# EFD01_-_C_Feeder.net
KiCad netlist of a schematic drawn in EAGLE
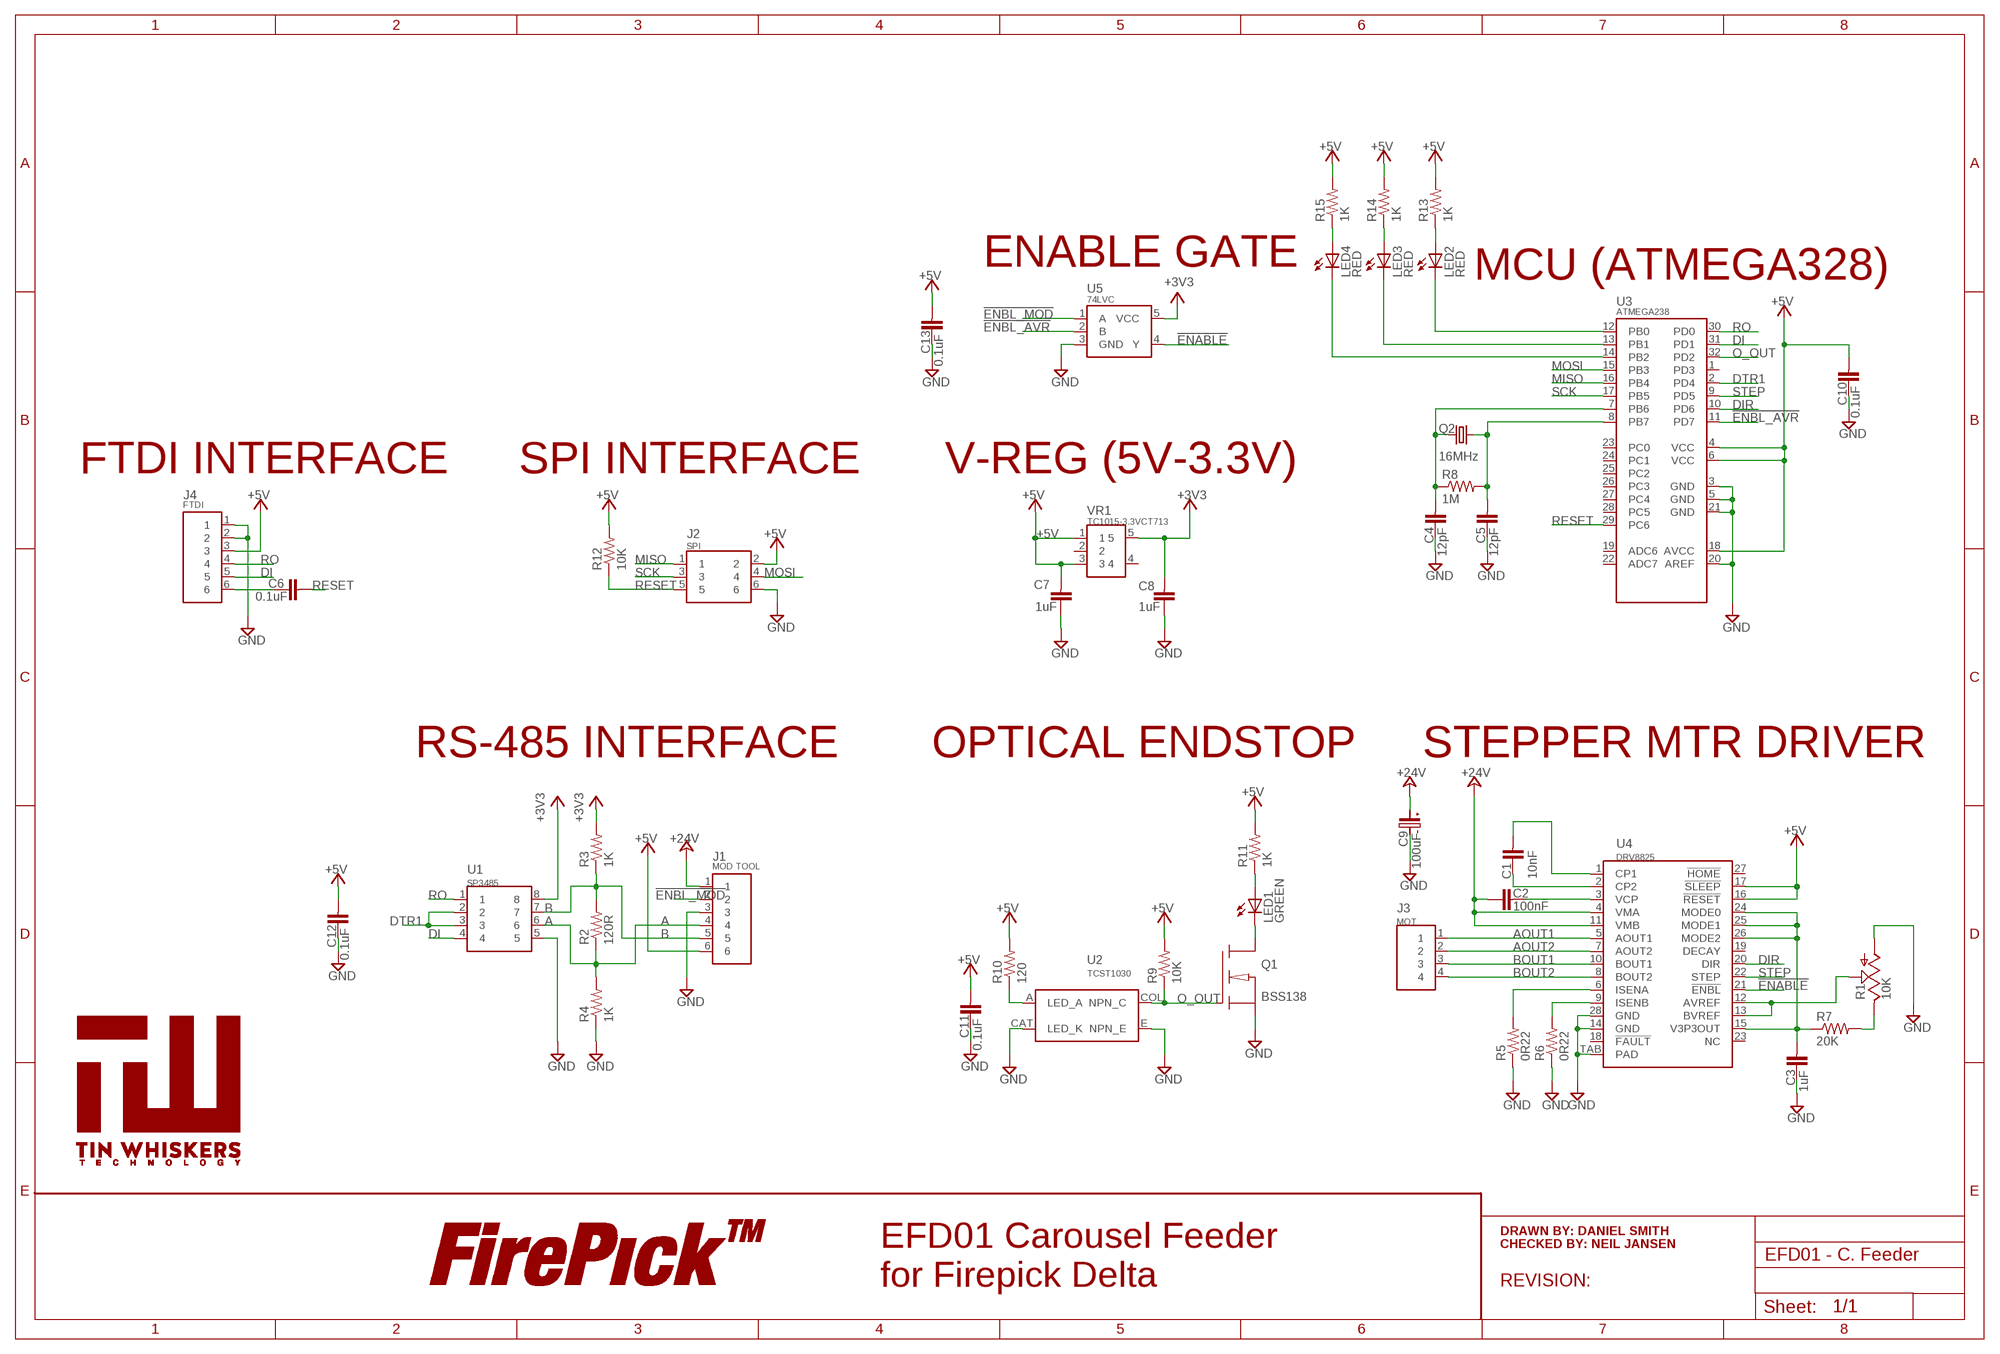
[diagram p0: schematic, sheet 1]

(export (version "E")
  (design (tool "Eeschema 10.0.6"))
  (components
    (comp (ref "C1")
      (value "10nF")
      (footprint "eagle-import:C0603")
      (fields (field (name "PARTNO") "GRM188R71H103KA01D"))
      (libsource (lib "eagle-import") (part "CPL-CAP-X7R-0603-10NF-50V"))
    )
    (comp (ref "C2")
      (value "100nF")
      (footprint "eagle-import:C0603")
      (fields (field (name "PARTNO") "UMK107B7104KA-T"))
      (libsource (lib "eagle-import") (part "CPL-CAP-X7R-0603-100NF-50V"))
    )
    (comp (ref "C3")
      (value "1uF")
      (footprint "eagle-import:C0603")
      (fields (field (name "PARTNO") "UMK107AB7105KA-T"))
      (libsource (lib "eagle-import") (part "CPL-CAP-X5R-0603-1UF-50V"))
    )
    (comp (ref "C4")
      (value "12pF")
      (footprint "eagle-import:C0603")
      (fields (field (name "PARTNO") "GRM1885C1H120FA01J"))
      (libsource (lib "eagle-import") (part "CPL-CAP-C0G-0603-12PF-50V"))
    )
    (comp (ref "C5")
      (value "12pF")
      (footprint "eagle-import:C0603")
      (fields (field (name "PARTNO") "GRM1885C1H120FA01J"))
      (libsource (lib "eagle-import") (part "CPL-CAP-C0G-0603-12PF-50V"))
    )
    (comp (ref "C6")
      (value "0.1uF")
      (footprint "eagle-import:C0603")
      (fields (field (name "PARTNO") "UMK107B7104KA-T"))
      (libsource (lib "eagle-import") (part "CPL-CAP-X7R-0603-100NF-50V"))
    )
    (comp (ref "C7")
      (value "1uF")
      (footprint "eagle-import:C0603")
      (fields (field (name "PARTNO") "UMK107AB7105KA-T"))
      (libsource (lib "eagle-import") (part "CPL-CAP-X5R-0603-1UF-50V"))
    )
    (comp (ref "C8")
      (value "1uF")
      (footprint "eagle-import:C0603")
      (fields (field (name "PARTNO") "UMK107AB7105KA-T"))
      (libsource (lib "eagle-import") (part "CPL-CAP-X5R-0603-1UF-50V"))
    )
    (comp (ref "C9")
      (value "100uF")
      (footprint "eagle-import:C-SMD-6.3MM")
      (fields (field (name "PARTNO") "EMVA500ADA101MHA0G"))
      (libsource (lib "eagle-import") (part "CPL-CAP-ALU-SMD-100UF-50V"))
    )
    (comp (ref "C10")
      (value "0.1uF")
      (footprint "eagle-import:C0603")
      (fields (field (name "PARTNO") "UMK107B7104KA-T"))
      (libsource (lib "eagle-import") (part "CPL-CAP-X7R-0603-0.1UF-35V"))
    )
    (comp (ref "C11")
      (value "0.1uF")
      (footprint "eagle-import:C0603")
      (fields (field (name "PARTNO") "UMK107B7104KA-T"))
      (libsource (lib "eagle-import") (part "CPL-CAP-X7R-0603-0.1UF-35V"))
    )
    (comp (ref "C12")
      (value "0.1uF")
      (footprint "eagle-import:C0603")
      (fields (field (name "PARTNO") "UMK107B7104KA-T"))
      (libsource (lib "eagle-import") (part "CPL-CAP-X7R-0603-0.1UF-35V"))
    )
    (comp (ref "C13")
      (value "0.1uF")
      (footprint "eagle-import:C0603")
      (fields (field (name "PARTNO") "UMK107B7104KA-T"))
      (libsource (lib "eagle-import") (part "CPL-CAP-X7R-0603-0.1UF-35V"))
    )
    (comp (ref "J1")
      (value "MOD TOOL")
      (footprint "eagle-import:CONN-JST-PH-2.0MM-6P-SMT-RA")
      (fields (field (name "PARTNO") "S6B-PH-SM4-TB(LF)(SN)"))
      (libsource (lib "eagle-import") (part "CPL-CON-JST-2.0MM-6P-M-RA"))
    )
    (comp (ref "J2")
      (value "SPI")
      (footprint "eagle-import:CON-HDR-2X3P")
      (fields (field (name "PARTNO") "67996-206HLF"))
      (libsource (lib "eagle-import") (part "CPL-CON-HEADER-0.1IN-2X3P-M"))
    )
    (comp (ref "J3")
      (value "MOT")
      (footprint "eagle-import:CONN-JST-PH-2.0MM-4P-SMT-RA")
      (fields (field (name "PARTNO") "S4B-PH-SM4-TB(LF)(SN)"))
      (libsource (lib "eagle-import") (part "CPL-CON-JST-2.0MM-4P-M-RA"))
    )
    (comp (ref "J4")
      (value "FTDI")
      (footprint "eagle-import:CON-HDR-6POS-MALE")
      (fields (field (name "PARTNO") "S6B-PH-SM4-TB(LF)(SN)"))
      (libsource (lib "eagle-import") (part "CPL-CON-HEADER-0.1IN-6P-M"))
    )
    (comp (ref "LED1")
      (value "GREEN")
      (footprint "eagle-import:LED0603")
      (fields (field (name "PARTNO") "SML-D12M8WT86"))
      (libsource (lib "eagle-import") (part "CPL-LED-0603-GREEN"))
    )
    (comp (ref "LED2")
      (value "RED")
      (footprint "eagle-import:LED0603")
      (fields (field (name "PARTNO") "SML-D12M8WT86"))
      (libsource (lib "eagle-import") (part "CPL-LED-0603-RED"))
    )
    (comp (ref "LED3")
      (value "RED")
      (footprint "eagle-import:LED0603")
      (fields (field (name "PARTNO") "SML-D12M8WT86"))
      (libsource (lib "eagle-import") (part "CPL-LED-0603-RED"))
    )
    (comp (ref "LED4")
      (value "RED")
      (footprint "eagle-import:LED0603")
      (fields (field (name "PARTNO") "SML-D12M8WT86"))
      (libsource (lib "eagle-import") (part "CPL-LED-0603-RED"))
    )
    (comp (ref "LOGO2")
      (value "LOGO-FIREPICKLARGE")
      (footprint "eagle-import:LOGO-FIREPICK")
      (libsource (lib "eagle-import") (part "LOGO-FIREPICKLARGE"))
    )
    (comp (ref "Q1")
      (value "BSS138")
      (footprint "eagle-import:SOT-23-3")
      (libsource (lib "eagle-import") (part "CPL-TRN-NFET-SOT23"))
    )
    (comp (ref "Q2")
      (value "16MHz")
      (footprint "eagle-import:HC-49_U-S")
      (fields (field (name "PARTNO") "HCM4916000000ABJT"))
      (libsource (lib "eagle-import") (part "CPL-OSC-CRY-16MHZ-18PF"))
    )
    (comp (ref "R1")
      (value "10K")
      (footprint "eagle-import:TC33X-2")
      (fields (field (name "PARTNO") "TC33X-2-103E"))
      (libsource (lib "eagle-import") (part "TC33X-2"))
    )
    (comp (ref "R2")
      (value "120R")
      (footprint "eagle-import:R0603")
      (fields (field (name "PARTNO") "RC0603FR-07120RL"))
      (libsource (lib "eagle-import") (part "CPL-RES-0603-120-0.1W"))
    )
    (comp (ref "R3")
      (value "1K")
      (footprint "eagle-import:R0603")
      (fields (field (name "PARTNO") "RC0603FR-071KL"))
      (libsource (lib "eagle-import") (part "CPL-RES-0603-1K-0.1W"))
    )
    (comp (ref "R4")
      (value "1K")
      (footprint "eagle-import:R0603")
      (fields (field (name "PARTNO") "RC0603FR-071KL"))
      (libsource (lib "eagle-import") (part "CPL-RES-0603-1K-0.1W"))
    )
    (comp (ref "R5")
      (value "0R22")
      (footprint "eagle-import:R1206")
      (fields (field (name "PARTNO") "RL1206FR-7W0R22L"))
      (libsource (lib "eagle-import") (part "CPL-RES-1206-0.22-0.5W"))
    )
    (comp (ref "R6")
      (value "0R22")
      (footprint "eagle-import:R1206")
      (fields (field (name "PARTNO") "RL1206FR-7W0R22L"))
      (libsource (lib "eagle-import") (part "CPL-RES-1206-0.22-0.5W"))
    )
    (comp (ref "R7")
      (value "20K")
      (footprint "eagle-import:R0603")
      (fields (field (name "PARTNO") "RC0603FR-0722KL"))
      (libsource (lib "eagle-import") (part "CPL-RES-0603-20K-0.1W"))
    )
    (comp (ref "R8")
      (value "1M")
      (footprint "eagle-import:R0603")
      (fields (field (name "PARTNO") "RC0603FR-071ML"))
      (libsource (lib "eagle-import") (part "CPL-RES-0603-1M-0.1W"))
    )
    (comp (ref "R9")
      (value "10K")
      (footprint "eagle-import:R0603")
      (fields (field (name "PARTNO") "RC0603FR-0710KL"))
      (libsource (lib "eagle-import") (part "CPL-RES-0603-10K-0.1W"))
    )
    (comp (ref "R10")
      (value "120")
      (footprint "eagle-import:R0603")
      (fields (field (name "PARTNO") "RC0603FR-07120RL"))
      (libsource (lib "eagle-import") (part "CPL-RES-0603-120-0.1W"))
    )
    (comp (ref "R11")
      (value "1K")
      (footprint "eagle-import:R0603")
      (fields (field (name "PARTNO") "RC0603FR-071KL"))
      (libsource (lib "eagle-import") (part "CPL-RES-0603-1K-0.1W"))
    )
    (comp (ref "R12")
      (value "10K")
      (footprint "eagle-import:R0603")
      (fields (field (name "PARTNO") "RC0603FR-0710KL"))
      (libsource (lib "eagle-import") (part "CPL-RES-0603-10K-0.1W"))
    )
    (comp (ref "R13")
      (value "1K")
      (footprint "eagle-import:R0603")
      (fields (field (name "PARTNO") "RC0603FR-071KL"))
      (libsource (lib "eagle-import") (part "CPL-RES-0603-1K-0.1W"))
    )
    (comp (ref "R14")
      (value "1K")
      (footprint "eagle-import:R0603")
      (fields (field (name "PARTNO") "RC0603FR-071KL"))
      (libsource (lib "eagle-import") (part "CPL-RES-0603-1K-0.1W"))
    )
    (comp (ref "R15")
      (value "1K")
      (footprint "eagle-import:R0603")
      (fields (field (name "PARTNO") "RC0603FR-071KL"))
      (libsource (lib "eagle-import") (part "CPL-RES-0603-1K-0.1W"))
    )
    (comp (ref "U$1")
      (value "TIN-WHISKERSSMALL")
      (footprint "eagle-import:TIN-WHISKERS-SMALL")
      (libsource (lib "eagle-import") (part "TIN-WHISKERSSMALL"))
    )
    (comp (ref "U1")
      (value "SP3485")
      (footprint "eagle-import:SOICN-8")
      (libsource (lib "eagle-import") (part "SP3485"))
    )
    (comp (ref "U2")
      (value "TCST1030")
      (footprint "eagle-import:TCST1030")
      (libsource (lib "eagle-import") (part "TCSTXX30"))
    )
    (comp (ref "U3")
      (value "ATMEGA238")
      (footprint "eagle-import:32-TQF(ATMEGA)")
      (fields (field (name "PARTNO") "ATMEGA328-AUR"))
      (libsource (lib "eagle-import") (part "CPL-MCU-ATMEL-AT328-32TQFP"))
    )
    (comp (ref "U4")
      (value "DRV8825")
      (footprint "eagle-import:28-HSSOP")
      (fields (field (name "PARTNO") "DRV8825PWPR"))
      (libsource (lib "eagle-import") (part "CPL-MDR-DRV8825"))
    )
    (comp (ref "U5")
      (value "74LVC")
      (footprint "eagle-import:SOT-23-5")
      (fields (field (name "PARTNO") "SN74LVC1G32DBVR"))
      (libsource (lib "eagle-import") (part "CPL-IC-LOGIC-OR-1CH-74LVC"))
    )
    (comp (ref "VR1")
      (value "TC1015-3.3VCT713")
      (footprint "eagle-import:SOT-23-5")
      (libsource (lib "eagle-import") (part "CPL-REG-LIN-3.3V-0.1A"))
    )
  )
  (nets
    (net (code "1") (name "+3V3") (class "Default")
      (node (ref "C8") (pin "2") (pinfunction "2_2") (pintype "passive"))
      (node (ref "R3") (pin "2") (pinfunction "2_2") (pintype "passive"))
      (node (ref "U1") (pin "8") (pinfunction "8_8") (pintype "bidirectional"))
      (node (ref "U5") (pin "5") (pinfunction "VCC_5") (pintype "bidirectional"))
      (node (ref "VR1") (pin "5") (pinfunction "5_5") (pintype "passive"))
    )
    (net (code "2") (name "+5V") (class "Default")
      (node (ref "C10") (pin "2") (pinfunction "2_2") (pintype "passive"))
      (node (ref "C11") (pin "2") (pinfunction "2_2") (pintype "passive"))
      (node (ref "C12") (pin "2") (pinfunction "2_2") (pintype "passive"))
      (node (ref "C13") (pin "2") (pinfunction "2_2") (pintype "passive"))
      (node (ref "C7") (pin "2") (pinfunction "2_2") (pintype "passive"))
      (node (ref "J1") (pin "6") (pinfunction "6_6") (pintype "bidirectional"))
      (node (ref "J2") (pin "2") (pinfunction "2_2") (pintype "passive"))
      (node (ref "J4") (pin "3") (pinfunction "3_3") (pintype "bidirectional"))
      (node (ref "R10") (pin "2") (pinfunction "2_2") (pintype "passive"))
      (node (ref "R11") (pin "2") (pinfunction "2_2") (pintype "passive"))
      (node (ref "R12") (pin "2") (pinfunction "2_2") (pintype "passive"))
      (node (ref "R13") (pin "2") (pinfunction "2_2") (pintype "passive"))
      (node (ref "R14") (pin "2") (pinfunction "2_2") (pintype "passive"))
      (node (ref "R15") (pin "2") (pinfunction "2_2") (pintype "passive"))
      (node (ref "R9") (pin "2") (pinfunction "2_2") (pintype "passive"))
      (node (ref "U3") (pin "18") (pinfunction "AVCC_18") (pintype "bidirectional"))
      (node (ref "U3") (pin "4") (pinfunction "VCC_4") (pintype "bidirectional"))
      (node (ref "U3") (pin "6") (pinfunction "VCC_6") (pintype "bidirectional"))
      (node (ref "U4") (pin "16") (pinfunction "~{RESET}_16") (pintype "bidirectional"))
      (node (ref "U4") (pin "17") (pinfunction "~{SLEEP}_17") (pintype "bidirectional"))
      (node (ref "VR1") (pin "1") (pinfunction "1_1") (pintype "passive"))
      (node (ref "VR1") (pin "3") (pinfunction "3_3") (pintype "passive"))
    )
    (net (code "3") (name "+24V") (class "Default")
      (node (ref "C2") (pin "1") (pinfunction "1_1") (pintype "passive"))
      (node (ref "C9") (pin "POS") (pinfunction "POS_POS") (pintype "passive"))
      (node (ref "J1") (pin "1") (pinfunction "1_1") (pintype "bidirectional"))
      (node (ref "U4") (pin "11") (pinfunction "VMB_11") (pintype "bidirectional"))
      (node (ref "U4") (pin "4") (pinfunction "VMA_4") (pintype "bidirectional"))
    )
    (net (code "4") (name "/A") (class "Default")
      (node (ref "J1") (pin "4") (pinfunction "4_4") (pintype "bidirectional"))
      (node (ref "R2") (pin "1") (pinfunction "1_1") (pintype "passive"))
      (node (ref "R4") (pin "2") (pinfunction "2_2") (pintype "passive"))
      (node (ref "U1") (pin "6") (pinfunction "6_6") (pintype "bidirectional"))
    )
    (net (code "5") (name "/AOUT1") (class "Default")
      (node (ref "J3") (pin "1") (pinfunction "1_1") (pintype "passive"))
      (node (ref "U4") (pin "5") (pinfunction "AOUT1_5") (pintype "bidirectional"))
    )
    (net (code "6") (name "/AOUT2") (class "Default")
      (node (ref "J3") (pin "2") (pinfunction "2_2") (pintype "passive"))
      (node (ref "U4") (pin "7") (pinfunction "AOUT2_7") (pintype "bidirectional"))
    )
    (net (code "7") (name "/B") (class "Default")
      (node (ref "J1") (pin "5") (pinfunction "5_5") (pintype "bidirectional"))
      (node (ref "R2") (pin "2") (pinfunction "2_2") (pintype "passive"))
      (node (ref "R3") (pin "1") (pinfunction "1_1") (pintype "passive"))
      (node (ref "U1") (pin "7") (pinfunction "7_7") (pintype "bidirectional"))
    )
    (net (code "8") (name "/BOUT1") (class "Default")
      (node (ref "J3") (pin "3") (pinfunction "3_3") (pintype "passive"))
      (node (ref "U4") (pin "10") (pinfunction "BOUT1_10") (pintype "bidirectional"))
    )
    (net (code "9") (name "/BOUT2") (class "Default")
      (node (ref "J3") (pin "4") (pinfunction "4_4") (pintype "passive"))
      (node (ref "U4") (pin "8") (pinfunction "BOUT2_8") (pintype "bidirectional"))
    )
    (net (code "10") (name "/DI") (class "Default")
      (node (ref "J4") (pin "5") (pinfunction "5_5") (pintype "bidirectional"))
      (node (ref "U1") (pin "4") (pinfunction "4_4") (pintype "bidirectional"))
      (node (ref "U3") (pin "31") (pinfunction "PD1_31") (pintype "bidirectional"))
    )
    (net (code "11") (name "/DIR") (class "Default")
      (node (ref "U3") (pin "10") (pinfunction "PD6_10") (pintype "bidirectional"))
      (node (ref "U4") (pin "20") (pinfunction "DIR_20") (pintype "bidirectional"))
    )
    (net (code "12") (name "/DTR1") (class "Default")
      (node (ref "U1") (pin "2") (pinfunction "2_2") (pintype "bidirectional"))
      (node (ref "U1") (pin "3") (pinfunction "3_3") (pintype "bidirectional"))
      (node (ref "U3") (pin "2") (pinfunction "PD4_2") (pintype "bidirectional"))
    )
    (net (code "13") (name "/MISO") (class "Default")
      (node (ref "J2") (pin "1") (pinfunction "1_1") (pintype "passive"))
      (node (ref "U3") (pin "16") (pinfunction "PB4_16") (pintype "bidirectional"))
    )
    (net (code "14") (name "/MOSI") (class "Default")
      (node (ref "J2") (pin "4") (pinfunction "4_4") (pintype "passive"))
      (node (ref "U3") (pin "15") (pinfunction "PB3_15") (pintype "bidirectional"))
    )
    (net (code "15") (name "/O_OUT") (class "Default")
      (node (ref "Q1") (pin "1") (pinfunction "G_1") (pintype "passive"))
      (node (ref "R9") (pin "1") (pinfunction "1_1") (pintype "passive"))
      (node (ref "U2") (pin "COL") (pinfunction "NPN_C_COL") (pintype "bidirectional"))
      (node (ref "U3") (pin "32") (pinfunction "PD2_32") (pintype "bidirectional"))
    )
    (net (code "16") (name "/RESET") (class "Default")
      (node (ref "C6") (pin "2") (pinfunction "2_2") (pintype "passive"))
      (node (ref "J2") (pin "5") (pinfunction "5_5") (pintype "passive"))
      (node (ref "R12") (pin "1") (pinfunction "1_1") (pintype "passive"))
      (node (ref "U3") (pin "29") (pinfunction "PC6_29") (pintype "bidirectional"))
    )
    (net (code "17") (name "/RO") (class "Default")
      (node (ref "J4") (pin "4") (pinfunction "4_4") (pintype "bidirectional"))
      (node (ref "U1") (pin "1") (pinfunction "1_1") (pintype "bidirectional"))
      (node (ref "U3") (pin "30") (pinfunction "PD0_30") (pintype "bidirectional"))
    )
    (net (code "18") (name "/SCK") (class "Default")
      (node (ref "J2") (pin "3") (pinfunction "3_3") (pintype "passive"))
      (node (ref "U3") (pin "17") (pinfunction "PB5_17") (pintype "bidirectional"))
    )
    (net (code "19") (name "/STEP") (class "Default")
      (node (ref "U3") (pin "9") (pinfunction "PD5_9") (pintype "bidirectional"))
      (node (ref "U4") (pin "22") (pinfunction "STEP_22") (pintype "bidirectional"))
    )
    (net (code "20") (name "/~{ENABLE}") (class "Default")
      (node (ref "U4") (pin "21") (pinfunction "~{ENBL}_21") (pintype "bidirectional"))
      (node (ref "U5") (pin "4") (pinfunction "Y_4") (pintype "bidirectional"))
    )
    (net (code "21") (name "/~{ENBL_AVR}") (class "Default")
      (node (ref "U3") (pin "11") (pinfunction "PD7_11") (pintype "bidirectional"))
      (node (ref "U5") (pin "2") (pinfunction "B_2") (pintype "bidirectional"))
    )
    (net (code "22") (name "/~{ENBL_MOD}") (class "Default")
      (node (ref "J1") (pin "2") (pinfunction "2_2") (pintype "bidirectional"))
      (node (ref "U5") (pin "1") (pinfunction "A_1") (pintype "bidirectional"))
    )
    (net (code "23") (name "GND") (class "Default")
      (node (ref "C10") (pin "1") (pinfunction "1_1") (pintype "passive"))
      (node (ref "C11") (pin "1") (pinfunction "1_1") (pintype "passive"))
      (node (ref "C12") (pin "1") (pinfunction "1_1") (pintype "passive"))
      (node (ref "C13") (pin "1") (pinfunction "1_1") (pintype "passive"))
      (node (ref "C3") (pin "1") (pinfunction "1_1") (pintype "passive"))
      (node (ref "C4") (pin "1") (pinfunction "1_1") (pintype "passive"))
      (node (ref "C5") (pin "1") (pinfunction "1_1") (pintype "passive"))
      (node (ref "C7") (pin "1") (pinfunction "1_1") (pintype "passive"))
      (node (ref "C8") (pin "1") (pinfunction "1_1") (pintype "passive"))
      (node (ref "C9") (pin "NEG") (pinfunction "NEG_NEG") (pintype "passive"))
      (node (ref "J1") (pin "3") (pinfunction "3_3") (pintype "bidirectional"))
      (node (ref "J2") (pin "6") (pinfunction "6_6") (pintype "passive"))
      (node (ref "J4") (pin "1") (pinfunction "1_1") (pintype "bidirectional"))
      (node (ref "J4") (pin "2") (pinfunction "2_2") (pintype "bidirectional"))
      (node (ref "Q1") (pin "2") (pinfunction "S_2") (pintype "passive"))
      (node (ref "R1") (pin "1") (pinfunction "A_1") (pintype "passive"))
      (node (ref "R4") (pin "1") (pinfunction "1_1") (pintype "passive"))
      (node (ref "R5") (pin "1") (pinfunction "1_1") (pintype "passive"))
      (node (ref "R6") (pin "1") (pinfunction "1_1") (pintype "passive"))
      (node (ref "U1") (pin "5") (pinfunction "5_5") (pintype "bidirectional"))
      (node (ref "U2") (pin "CAT") (pinfunction "LED_K_CAT") (pintype "bidirectional"))
      (node (ref "U2") (pin "E") (pinfunction "NPN_E_E") (pintype "bidirectional"))
      (node (ref "U3") (pin "20") (pinfunction "AREF_20") (pintype "bidirectional"))
      (node (ref "U3") (pin "21") (pinfunction "GND_21") (pintype "bidirectional"))
      (node (ref "U3") (pin "3") (pinfunction "GND_3") (pintype "bidirectional"))
      (node (ref "U3") (pin "5") (pinfunction "GND_5") (pintype "bidirectional"))
      (node (ref "U4") (pin "14") (pinfunction "GND_14") (pintype "bidirectional"))
      (node (ref "U4") (pin "28") (pinfunction "GND_28") (pintype "bidirectional"))
      (node (ref "U4") (pin "TAB") (pinfunction "PAD_TAB") (pintype "bidirectional"))
      (node (ref "U5") (pin "3") (pinfunction "GND_3") (pintype "bidirectional"))
    )
    (net (code "24") (name "Net-(C6-Pad1)") (class "Default")
      (node (ref "C6") (pin "1") (pinfunction "1_1") (pintype "passive"))
      (node (ref "J4") (pin "6") (pinfunction "6_6") (pintype "bidirectional"))
    )
    (net (code "25") (name "Net-(LED1-PadA)") (class "Default")
      (node (ref "LED1") (pin "A") (pinfunction "A_A") (pintype "passive"))
      (node (ref "R11") (pin "1") (pinfunction "1_1") (pintype "passive"))
    )
    (net (code "26") (name "Net-(LED2-PadA)") (class "Default")
      (node (ref "LED2") (pin "A") (pinfunction "A_A") (pintype "passive"))
      (node (ref "R13") (pin "1") (pinfunction "1_1") (pintype "passive"))
    )
    (net (code "27") (name "Net-(LED3-PadA)") (class "Default")
      (node (ref "LED3") (pin "A") (pinfunction "A_A") (pintype "passive"))
      (node (ref "R14") (pin "1") (pinfunction "1_1") (pintype "passive"))
    )
    (net (code "28") (name "Net-(LED4-PadA)") (class "Default")
      (node (ref "LED4") (pin "A") (pinfunction "A_A") (pintype "passive"))
      (node (ref "R15") (pin "1") (pinfunction "1_1") (pintype "passive"))
    )
    (net (code "29") (name "Net-(Q1-D)") (class "Default")
      (node (ref "LED1") (pin "C") (pinfunction "C_C") (pintype "passive"))
      (node (ref "Q1") (pin "3") (pinfunction "D_3") (pintype "passive"))
    )
    (net (code "30") (name "Net-(R1-E)") (class "Default")
      (node (ref "R1") (pin "3") (pinfunction "E_3") (pintype "passive"))
      (node (ref "R7") (pin "2") (pinfunction "2_2") (pintype "passive"))
    )
    (net (code "31") (name "Net-(R1-S)") (class "Default")
      (node (ref "R1") (pin "2") (pinfunction "S_2") (pintype "passive"))
      (node (ref "U4") (pin "12") (pinfunction "AVREF_12") (pintype "bidirectional"))
      (node (ref "U4") (pin "13") (pinfunction "BVREF_13") (pintype "bidirectional"))
    )
    (net (code "32") (name "Net-(U2-LED_A)") (class "Default")
      (node (ref "R10") (pin "1") (pinfunction "1_1") (pintype "passive"))
      (node (ref "U2") (pin "A") (pinfunction "LED_A_A") (pintype "bidirectional"))
    )
    (net (code "33") (name "Net-(U3-PB0)") (class "Default")
      (node (ref "LED2") (pin "C") (pinfunction "C_C") (pintype "passive"))
      (node (ref "U3") (pin "12") (pinfunction "PB0_12") (pintype "bidirectional"))
    )
    (net (code "34") (name "Net-(U3-PB1)") (class "Default")
      (node (ref "LED3") (pin "C") (pinfunction "C_C") (pintype "passive"))
      (node (ref "U3") (pin "13") (pinfunction "PB1_13") (pintype "bidirectional"))
    )
    (net (code "35") (name "Net-(U3-PB2)") (class "Default")
      (node (ref "LED4") (pin "C") (pinfunction "C_C") (pintype "passive"))
      (node (ref "U3") (pin "14") (pinfunction "PB2_14") (pintype "bidirectional"))
    )
    (net (code "36") (name "Net-(U3-PB6)") (class "Default")
      (node (ref "C4") (pin "2") (pinfunction "2_2") (pintype "passive"))
      (node (ref "Q2") (pin "1") (pinfunction "1_1") (pintype "passive"))
      (node (ref "R8") (pin "1") (pinfunction "1_1") (pintype "passive"))
      (node (ref "U3") (pin "7") (pinfunction "PB6_7") (pintype "bidirectional"))
    )
    (net (code "37") (name "Net-(U3-PB7)") (class "Default")
      (node (ref "C5") (pin "2") (pinfunction "2_2") (pintype "passive"))
      (node (ref "Q2") (pin "2") (pinfunction "2_2") (pintype "passive"))
      (node (ref "R8") (pin "2") (pinfunction "2_2") (pintype "passive"))
      (node (ref "U3") (pin "8") (pinfunction "PB7_8") (pintype "bidirectional"))
    )
    (net (code "38") (name "Net-(U4-CP1)") (class "Default")
      (node (ref "C1") (pin "2") (pinfunction "2_2") (pintype "passive"))
      (node (ref "U4") (pin "1") (pinfunction "CP1_1") (pintype "bidirectional"))
    )
    (net (code "39") (name "Net-(U4-CP2)") (class "Default")
      (node (ref "C1") (pin "1") (pinfunction "1_1") (pintype "passive"))
      (node (ref "U4") (pin "2") (pinfunction "CP2_2") (pintype "bidirectional"))
    )
    (net (code "40") (name "Net-(U4-ISENA)") (class "Default")
      (node (ref "R5") (pin "2") (pinfunction "2_2") (pintype "passive"))
      (node (ref "U4") (pin "6") (pinfunction "ISENA_6") (pintype "bidirectional"))
    )
    (net (code "41") (name "Net-(U4-ISENB)") (class "Default")
      (node (ref "R6") (pin "2") (pinfunction "2_2") (pintype "passive"))
      (node (ref "U4") (pin "9") (pinfunction "ISENB_9") (pintype "bidirectional"))
    )
    (net (code "42") (name "Net-(U4-MODE0)") (class "Default")
      (node (ref "C3") (pin "2") (pinfunction "2_2") (pintype "passive"))
      (node (ref "R7") (pin "1") (pinfunction "1_1") (pintype "passive"))
      (node (ref "U4") (pin "15") (pinfunction "V3P3OUT_15") (pintype "bidirectional"))
      (node (ref "U4") (pin "24") (pinfunction "MODE0_24") (pintype "bidirectional"))
      (node (ref "U4") (pin "25") (pinfunction "MODE1_25") (pintype "bidirectional"))
      (node (ref "U4") (pin "26") (pinfunction "MODE2_26") (pintype "bidirectional"))
    )
    (net (code "43") (name "Net-(U4-VCP)") (class "Default")
      (node (ref "C2") (pin "2") (pinfunction "2_2") (pintype "passive"))
      (node (ref "U4") (pin "3") (pinfunction "VCP_3") (pintype "bidirectional"))
    )
    (net (code "44") (name "unconnected-(U3-ADC6-Pad19)") (class "Default")
      (node (ref "U3") (pin "19") (pinfunction "ADC6_19") (pintype "bidirectional"))
    )
    (net (code "45") (name "unconnected-(U3-ADC7-Pad22)") (class "Default")
      (node (ref "U3") (pin "22") (pinfunction "ADC7_22") (pintype "bidirectional"))
    )
    (net (code "46") (name "unconnected-(U3-PC0-Pad23)") (class "Default")
      (node (ref "U3") (pin "23") (pinfunction "PC0_23") (pintype "bidirectional"))
    )
    (net (code "47") (name "unconnected-(U3-PC1-Pad24)") (class "Default")
      (node (ref "U3") (pin "24") (pinfunction "PC1_24") (pintype "bidirectional"))
    )
    (net (code "48") (name "unconnected-(U3-PC2-Pad25)") (class "Default")
      (node (ref "U3") (pin "25") (pinfunction "PC2_25") (pintype "bidirectional"))
    )
    (net (code "49") (name "unconnected-(U3-PC3-Pad26)") (class "Default")
      (node (ref "U3") (pin "26") (pinfunction "PC3_26") (pintype "bidirectional"))
    )
    (net (code "50") (name "unconnected-(U3-PC4-Pad27)") (class "Default")
      (node (ref "U3") (pin "27") (pinfunction "PC4_27") (pintype "bidirectional"))
    )
    (net (code "51") (name "unconnected-(U3-PC5-Pad28)") (class "Default")
      (node (ref "U3") (pin "28") (pinfunction "PC5_28") (pintype "bidirectional"))
    )
    (net (code "52") (name "unconnected-(U3-PD3-Pad1)") (class "Default")
      (node (ref "U3") (pin "1") (pinfunction "PD3_1") (pintype "bidirectional"))
    )
    (net (code "53") (name "unconnected-(U4-DECAY-Pad19)") (class "Default")
      (node (ref "U4") (pin "19") (pinfunction "DECAY_19") (pintype "bidirectional"))
    )
    (net (code "54") (name "unconnected-(U4-NC-Pad23)") (class "Default")
      (node (ref "U4") (pin "23") (pinfunction "NC_23") (pintype "bidirectional"))
    )
    (net (code "55") (name "unconnected-(U4-~{FAULT}-Pad18)") (class "Default")
      (node (ref "U4") (pin "18") (pinfunction "~{FAULT}_18") (pintype "bidirectional"))
    )
    (net (code "56") (name "unconnected-(U4-~{HOME}-Pad27)") (class "Default")
      (node (ref "U4") (pin "27") (pinfunction "~{HOME}_27") (pintype "bidirectional"))
    )
    (net (code "57") (name "unconnected-(VR1-Pad2)") (class "Default")
      (node (ref "VR1") (pin "2") (pinfunction "2_2") (pintype "passive"))
    )
    (net (code "58") (name "unconnected-(VR1-Pad4)") (class "Default")
      (node (ref "VR1") (pin "4") (pinfunction "4_4") (pintype "passive"))
    )
  )
)
